# TelecarMasterDriverStc8051.net
KiCad netlist of a schematic drawn in Altium Designer
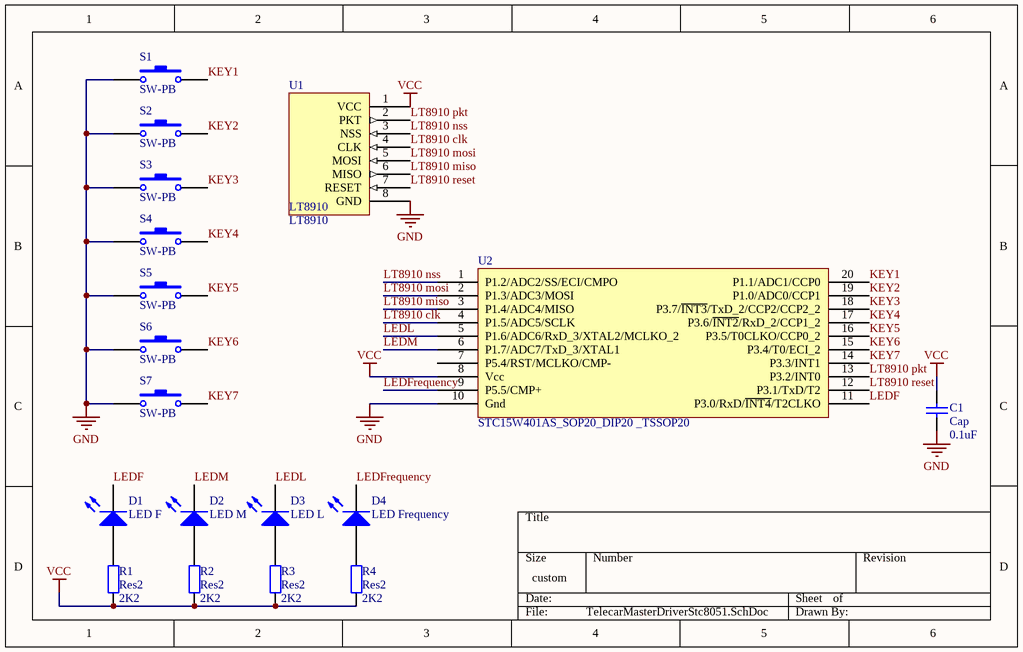
[diagram p0: TelecarMasterDriverStc8051.SchDoc]

(export (version "E")
  (design (tool "Eeschema 10.0.6"))
  (components
    (comp (ref "C1")
      (value "Cap")
      (footprint "RAD-0.3")
      (description "Capacitor")
      (fields (field (name "ALTIUM_VALUE") "0.1uF") (field (name "PUBLISHER") "Altium Limited"))
      (libsource (lib "Miscellaneous Devices") (part "Cap"))
    )
    (comp (ref "D1")
      (value "LED F")
      (footprint "LED-1")
      (description "Typical RED GaAs LED")
      (fields (field (name "PUBLISHER") "Altium Limited"))
      (libsource (lib "Miscellaneous Devices") (part "LED1"))
    )
    (comp (ref "D2")
      (value "LED M")
      (footprint "LED-1")
      (description "Typical RED GaAs LED")
      (fields (field (name "PUBLISHER") "Altium Limited"))
      (libsource (lib "Miscellaneous Devices") (part "LED1"))
    )
    (comp (ref "D3")
      (value "LED L")
      (footprint "LED-1")
      (description "Typical RED GaAs LED")
      (fields (field (name "PUBLISHER") "Altium Limited"))
      (libsource (lib "Miscellaneous Devices") (part "LED1"))
    )
    (comp (ref "D4")
      (value "LED Frequency")
      (footprint "LED-1")
      (description "Typical RED GaAs LED")
      (fields (field (name "PUBLISHER") "Altium Limited"))
      (libsource (lib "Miscellaneous Devices") (part "LED1"))
    )
    (comp (ref "R1")
      (value "Res2")
      (footprint "AXIAL-0.4")
      (description "Resistor")
      (fields (field (name "ALTIUM_VALUE") "2K2") (field (name "PUBLISHER") "Altium Limited"))
      (libsource (lib "Miscellaneous Devices") (part "Res2"))
    )
    (comp (ref "R2")
      (value "Res2")
      (footprint "AXIAL-0.4")
      (description "Resistor")
      (fields (field (name "ALTIUM_VALUE") "2K2") (field (name "PUBLISHER") "Altium Limited"))
      (libsource (lib "Miscellaneous Devices") (part "Res2"))
    )
    (comp (ref "R3")
      (value "Res2")
      (footprint "AXIAL-0.4")
      (description "Resistor")
      (fields (field (name "ALTIUM_VALUE") "2K2") (field (name "PUBLISHER") "Altium Limited"))
      (libsource (lib "Miscellaneous Devices") (part "Res2"))
    )
    (comp (ref "R4")
      (value "Res2")
      (footprint "AXIAL-0.4")
      (description "Resistor")
      (fields (field (name "ALTIUM_VALUE") "2K2") (field (name "PUBLISHER") "Altium Limited"))
      (libsource (lib "Miscellaneous Devices") (part "Res2"))
    )
    (comp (ref "S1")
      (value "SW-PB")
      (footprint "SPST-2")
      (description "Switch")
      (fields (field (name "PUBLISHER") "Altium Limited"))
      (libsource (lib "Miscellaneous Devices") (part "SW-PB"))
    )
    (comp (ref "S2")
      (value "SW-PB")
      (footprint "SPST-2")
      (description "Switch")
      (fields (field (name "PUBLISHER") "Altium Limited"))
      (libsource (lib "Miscellaneous Devices") (part "SW-PB"))
    )
    (comp (ref "S3")
      (value "SW-PB")
      (footprint "SPST-2")
      (description "Switch")
      (fields (field (name "PUBLISHER") "Altium Limited"))
      (libsource (lib "Miscellaneous Devices") (part "SW-PB"))
    )
    (comp (ref "S4")
      (value "SW-PB")
      (footprint "SPST-2")
      (description "Switch")
      (fields (field (name "PUBLISHER") "Altium Limited"))
      (libsource (lib "Miscellaneous Devices") (part "SW-PB"))
    )
    (comp (ref "S5")
      (value "SW-PB")
      (footprint "SPST-2")
      (description "Switch")
      (fields (field (name "PUBLISHER") "Altium Limited"))
      (libsource (lib "Miscellaneous Devices") (part "SW-PB"))
    )
    (comp (ref "S6")
      (value "SW-PB")
      (footprint "SPST-2")
      (description "Switch")
      (fields (field (name "PUBLISHER") "Altium Limited"))
      (libsource (lib "Miscellaneous Devices") (part "SW-PB"))
    )
    (comp (ref "S7")
      (value "SW-PB")
      (footprint "SPST-2")
      (description "Switch")
      (fields (field (name "PUBLISHER") "Altium Limited"))
      (libsource (lib "Miscellaneous Devices") (part "SW-PB"))
    )
    (comp (ref "U1") (value "LT8910") (libsource (lib "glib") (part "LT8910")))
    (comp (ref "U2")
      (value "STC15W401AS_SOP20_DIP20 _TSSOP20")
      (footprint "TSSOP20")
      (libsource (lib "stcmcu_altium_lib") (part "STC15W401AS_SOP20_DIP20 _TSSOP20"))
    )
  )
  (nets
    (net (code "1") (name "/KEY1") (class "Default")
      (node (ref "S1") (pin "2") (pinfunction "2_2") (pintype "passive"))
      (node (ref "U2") (pin "20") (pinfunction "P1.1/ADC1/CCP0_20") (pintype "passive"))
    )
    (net (code "2") (name "/KEY2") (class "Default")
      (node (ref "S2") (pin "2") (pinfunction "2_2") (pintype "passive"))
      (node (ref "U2") (pin "19") (pinfunction "P1.0/ADC0/CCP1_19") (pintype "passive"))
    )
    (net (code "3") (name "/KEY3") (class "Default")
      (node (ref "S3") (pin "2") (pinfunction "2_2") (pintype "passive"))
      (node (ref "U2") (pin "18") (pinfunction "P3.7/~{INT3}/TxD_2/CCP2/CCP2_2_18") (pintype "passive"))
    )
    (net (code "4") (name "/KEY4") (class "Default")
      (node (ref "S4") (pin "2") (pinfunction "2_2") (pintype "passive"))
      (node (ref "U2") (pin "17") (pinfunction "P3.6/~{INT2}/RxD_2/CCP1_2_17") (pintype "passive"))
    )
    (net (code "5") (name "/KEY5") (class "Default")
      (node (ref "S5") (pin "2") (pinfunction "2_2") (pintype "passive"))
      (node (ref "U2") (pin "16") (pinfunction "P3.5/T0CLKO/CCP0_2_16") (pintype "passive"))
    )
    (net (code "6") (name "/KEY6") (class "Default")
      (node (ref "S6") (pin "2") (pinfunction "2_2") (pintype "passive"))
      (node (ref "U2") (pin "15") (pinfunction "P3.4/T0/ECI_2_15") (pintype "passive"))
    )
    (net (code "7") (name "/KEY7") (class "Default")
      (node (ref "S7") (pin "2") (pinfunction "2_2") (pintype "passive"))
      (node (ref "U2") (pin "14") (pinfunction "P3.3/INT1_14") (pintype "passive"))
    )
    (net (code "8") (name "/LEDF") (class "Default")
      (node (ref "D1") (pin "2") (pinfunction "K_2") (pintype "passive"))
      (node (ref "U2") (pin "11") (pinfunction "P3.0/RxD/~{INT4}/T2CLKO_11") (pintype "passive"))
    )
    (net (code "9") (name "/LEDFrequency") (class "Default")
      (node (ref "D4") (pin "2") (pinfunction "K_2") (pintype "passive"))
      (node (ref "U2") (pin "9") (pinfunction "P5.5/CMP+_9") (pintype "passive"))
    )
    (net (code "10") (name "/LEDL") (class "Default")
      (node (ref "D3") (pin "2") (pinfunction "K_2") (pintype "passive"))
      (node (ref "U2") (pin "5") (pinfunction "P1.6/ADC6/RxD_3/XTAL2/MCLKO_2_5") (pintype "passive"))
    )
    (net (code "11") (name "/LEDM") (class "Default")
      (node (ref "D2") (pin "2") (pinfunction "K_2") (pintype "passive"))
      (node (ref "U2") (pin "6") (pinfunction "P1.7/ADC7/TxD_3/XTAL1_6") (pintype "passive"))
    )
    (net (code "12") (name "/LT8910 clk") (class "Default")
      (node (ref "U1") (pin "4") (pinfunction "CLK_4") (pintype "input"))
      (node (ref "U2") (pin "4") (pinfunction "P1.5/ADC5/SCLK_4") (pintype "passive"))
    )
    (net (code "13") (name "/LT8910 miso") (class "Default")
      (node (ref "U1") (pin "6") (pinfunction "MISO_6") (pintype "output"))
      (node (ref "U2") (pin "3") (pinfunction "P1.4/ADC4/MISO_3") (pintype "passive"))
    )
    (net (code "14") (name "/LT8910 mosi") (class "Default")
      (node (ref "U1") (pin "5") (pinfunction "MOSI_5") (pintype "input"))
      (node (ref "U2") (pin "2") (pinfunction "P1.3/ADC3/MOSI_2") (pintype "passive"))
    )
    (net (code "15") (name "/LT8910 nss") (class "Default")
      (node (ref "U1") (pin "3") (pinfunction "NSS_3") (pintype "input"))
      (node (ref "U2") (pin "1") (pinfunction "P1.2/ADC2/SS/ECI/CMPO_1") (pintype "passive"))
    )
    (net (code "16") (name "/LT8910 pkt") (class "Default")
      (node (ref "U1") (pin "2") (pinfunction "PKT_2") (pintype "output"))
      (node (ref "U2") (pin "13") (pinfunction "P3.2/INT0_13") (pintype "passive"))
    )
    (net (code "17") (name "/LT8910 reset") (class "Default")
      (node (ref "U1") (pin "7") (pinfunction "RESET_7") (pintype "input"))
      (node (ref "U2") (pin "12") (pinfunction "P3.1/TxD/T2_12") (pintype "passive"))
    )
    (net (code "18") (name "GND") (class "Default")
      (node (ref "C1") (pin "1") (pinfunction "1_1") (pintype "passive"))
      (node (ref "S1") (pin "1") (pinfunction "1_1") (pintype "passive"))
      (node (ref "S2") (pin "1") (pinfunction "1_1") (pintype "passive"))
      (node (ref "S3") (pin "1") (pinfunction "1_1") (pintype "passive"))
      (node (ref "S4") (pin "1") (pinfunction "1_1") (pintype "passive"))
      (node (ref "S5") (pin "1") (pinfunction "1_1") (pintype "passive"))
      (node (ref "S6") (pin "1") (pinfunction "1_1") (pintype "passive"))
      (node (ref "S7") (pin "1") (pinfunction "1_1") (pintype "passive"))
      (node (ref "U1") (pin "8") (pinfunction "GND_8") (pintype "power_in"))
      (node (ref "U2") (pin "10") (pinfunction "Gnd_10") (pintype "passive"))
    )
    (net (code "19") (name "Net-(D1-A)") (class "Default")
      (node (ref "D1") (pin "1") (pinfunction "A_1") (pintype "passive"))
      (node (ref "R1") (pin "2") (pinfunction "2_2") (pintype "passive"))
    )
    (net (code "20") (name "Net-(D2-A)") (class "Default")
      (node (ref "D2") (pin "1") (pinfunction "A_1") (pintype "passive"))
      (node (ref "R2") (pin "2") (pinfunction "2_2") (pintype "passive"))
    )
    (net (code "21") (name "Net-(D3-A)") (class "Default")
      (node (ref "D3") (pin "1") (pinfunction "A_1") (pintype "passive"))
      (node (ref "R3") (pin "2") (pinfunction "2_2") (pintype "passive"))
    )
    (net (code "22") (name "Net-(D4-A)") (class "Default")
      (node (ref "D4") (pin "1") (pinfunction "A_1") (pintype "passive"))
      (node (ref "R4") (pin "2") (pinfunction "2_2") (pintype "passive"))
    )
    (net (code "23") (name "VCC") (class "Default")
      (node (ref "C1") (pin "2") (pinfunction "2_2") (pintype "passive"))
      (node (ref "R1") (pin "1") (pinfunction "1_1") (pintype "passive"))
      (node (ref "R2") (pin "1") (pinfunction "1_1") (pintype "passive"))
      (node (ref "R3") (pin "1") (pinfunction "1_1") (pintype "passive"))
      (node (ref "R4") (pin "1") (pinfunction "1_1") (pintype "passive"))
      (node (ref "U1") (pin "1") (pinfunction "VCC_1") (pintype "power_in"))
      (node (ref "U2") (pin "8") (pinfunction "Vcc_8") (pintype "passive"))
    )
    (net (code "24") (name "unconnected-(U2-P5.4{slash}RST{slash}MCLKO{slash}CMP--Pad7)") (class "Default")
      (node (ref "U2") (pin "7") (pinfunction "P5.4/RST/MCLKO/CMP-_7") (pintype "passive"))
    )
  )
)
